# SAMV71_Xplained_Ultra_EDBG.net
KiCad netlist of a schematic drawn in Altium Designer
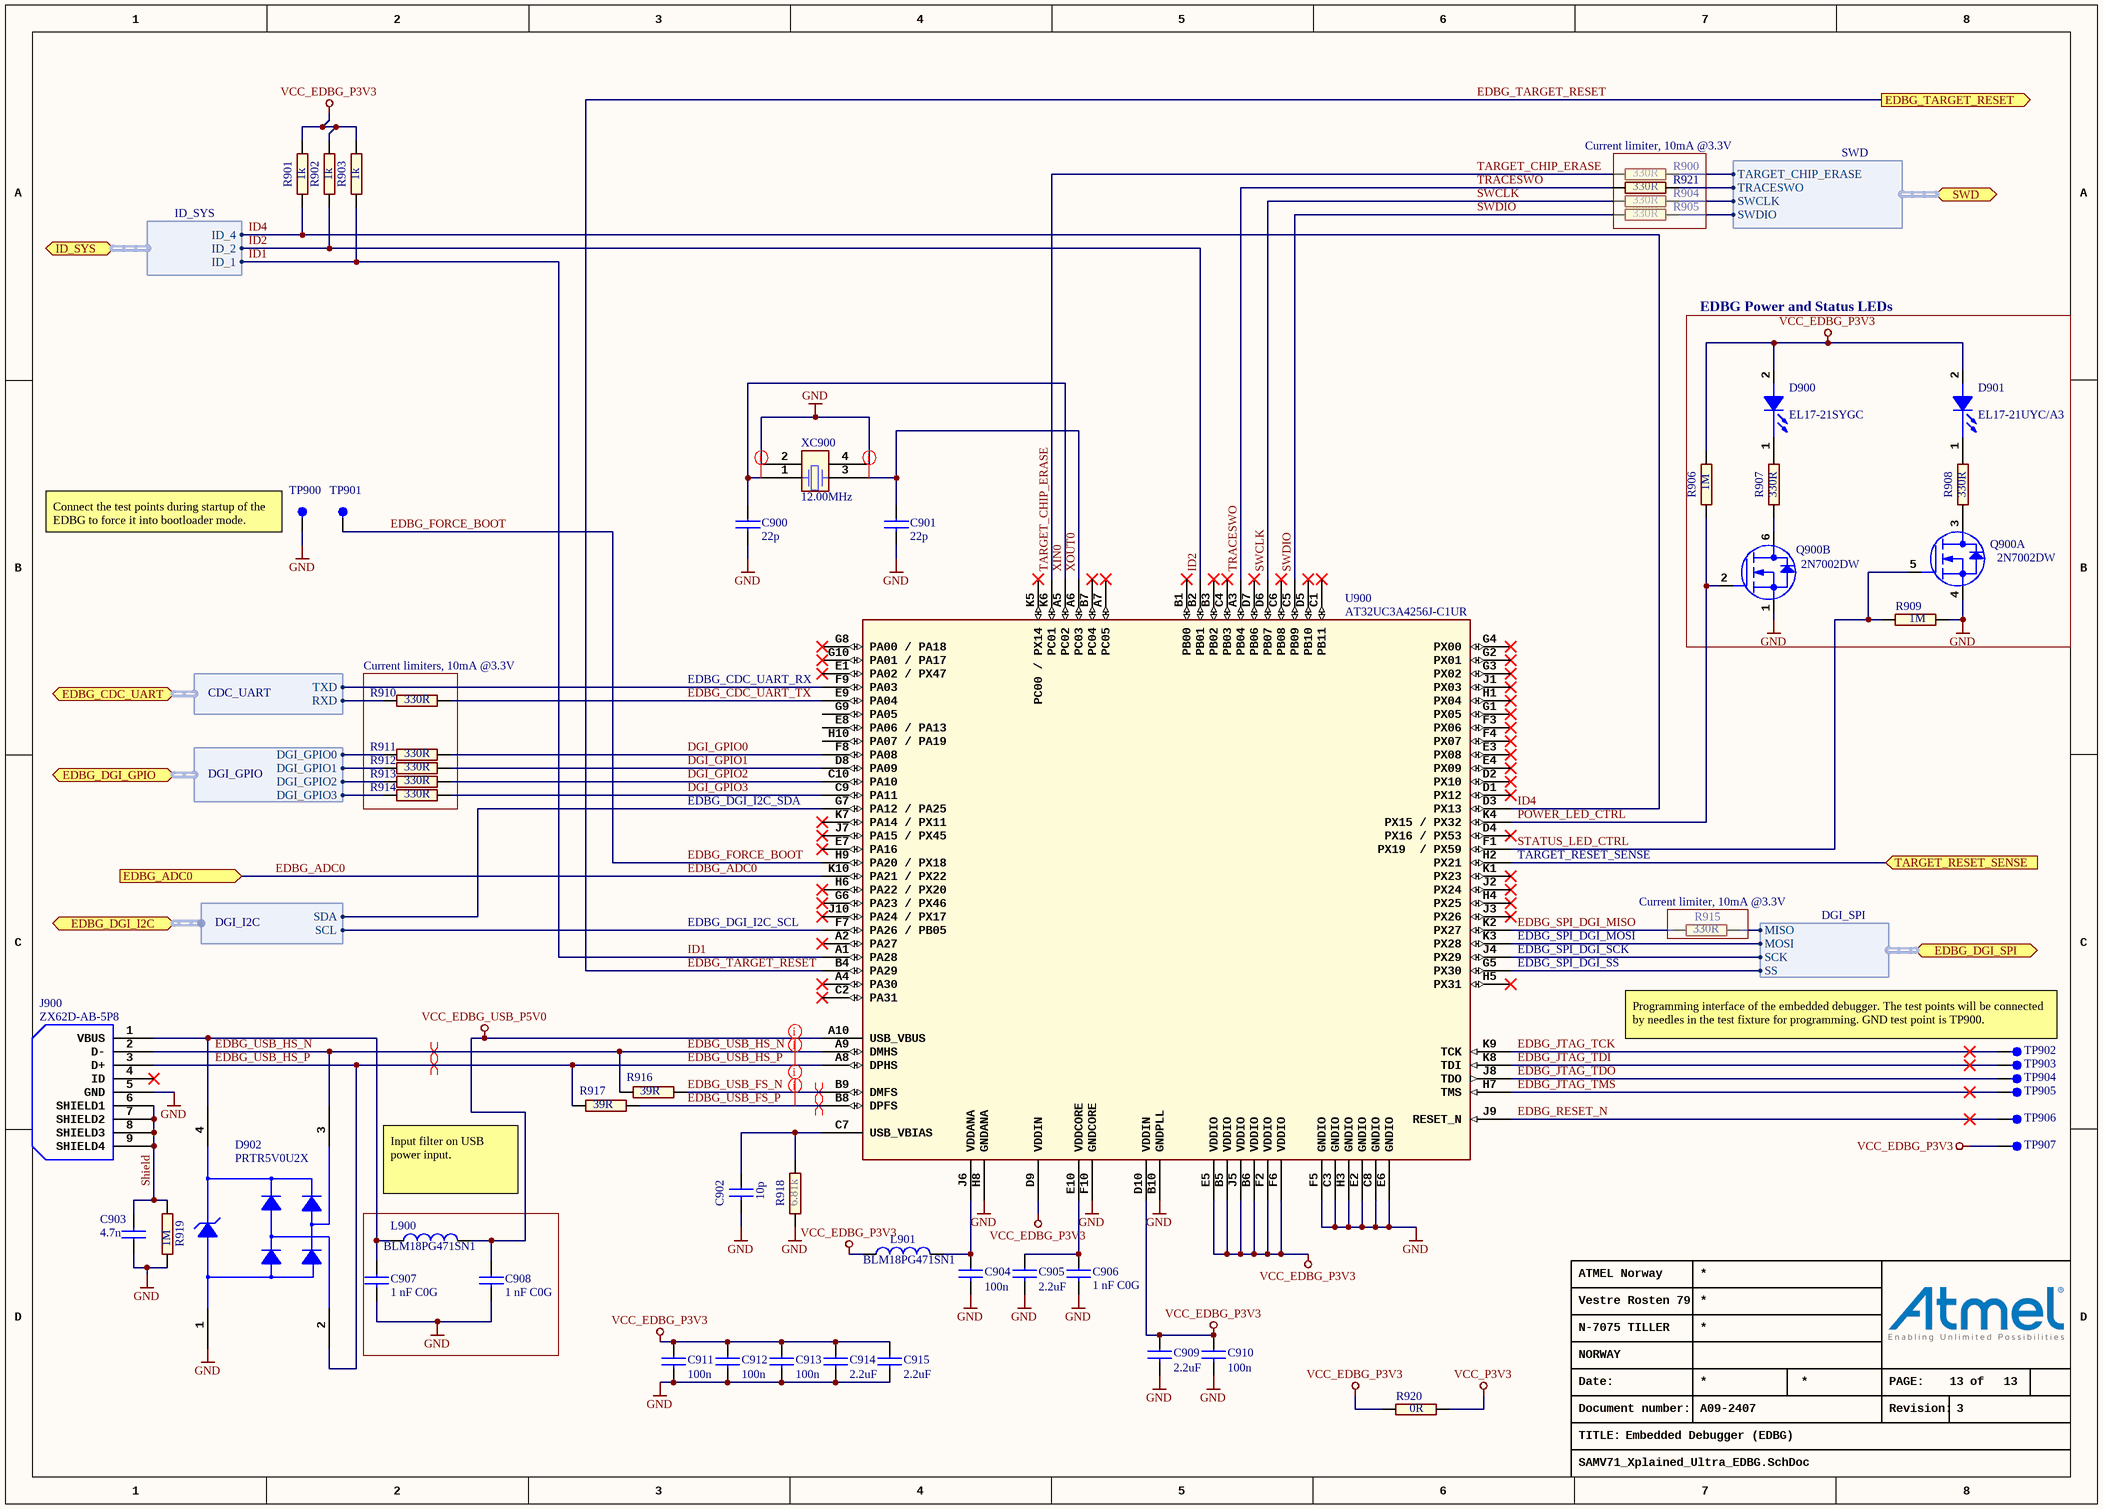
[diagram p0: SAMV71_Xplained_Ultra_EDBG.SchDoc]

(export (version "E")
  (design (tool "Eeschema 10.0.6"))
  (components
    (comp (ref "C900")
      (value "22p")
      (footprint "AP1-00053")
      (description "Ceramic capacitor, SMD 0402, NP0, 50V, +/-5%")
      (fields (field (name "TOLERANCE") "50V, +/-5%"))
      (libsource (lib "AltiumDbLib") (part "CAP-NONPOL"))
    )
    (comp (ref "C901")
      (value "22p")
      (footprint "AP1-00053")
      (description "Ceramic capacitor, SMD 0402, NP0, 50V, +/-5%")
      (fields (field (name "TOLERANCE") "50V, +/-5%"))
      (libsource (lib "AltiumDbLib") (part "CAP-NONPOL"))
    )
    (comp (ref "C902")
      (value "10p")
      (footprint "AP1-00053")
      (description "Ceramic capacitor, SMD 0402, NP0, 50V, +/-5%")
      (fields (field (name "TOLERANCE") "50V, +/-5%"))
      (libsource (lib "AltiumDbLib") (part "CAP-NONPOL"))
    )
    (comp (ref "C903")
      (value "4.7n")
      (footprint "AP1-00053")
      (description "Ceramic capacitor, SMD 0402, X7R, 25V, +/-10%")
      (fields (field (name "TOLERANCE") "25V, +/-10%"))
      (libsource (lib "AltiumDbLib") (part "CAP-NONPOL"))
    )
    (comp (ref "C904")
      (value "100n")
      (footprint "AP1-00053")
      (description "Ceramic capacitor, SMD 0402, X7R, 16V, +/-10%")
      (fields (field (name "TOLERANCE") "16V, +/-10%") (field (name "MANUFACTURER") "Kemet"))
      (libsource (lib "AltiumDbLib") (part "CAP-NONPOL"))
    )
    (comp (ref "C905")
      (value "2.2uF")
      (footprint "AP1-00053")
      (description "Ceramic capacitor, SMD 0402, X5R, 6.3V, +/-20%")
      (fields (field (name "TOLERANCE") "Â±20%") (field (name "MANUFACTURER") "Kemet"))
      (libsource (lib "AltiumDbLib") (part "CAP-NONPOL"))
    )
    (comp (ref "C906")
      (value "1 nF C0G")
      (footprint "AP1-00053")
      (description "Ceramic capacitor, SMD 0402, C0G, 50V, +/-5%")
      (fields (field (name "TOLERANCE") "5%") (field (name "MANUFACTURER") "Murata"))
      (libsource (lib "AltiumDbLib") (part "CAP-NONPOL"))
    )
    (comp (ref "C907")
      (value "1 nF C0G")
      (footprint "AP1-00053")
      (description "Ceramic capacitor, SMD 0402, C0G, 50V, +/-5%")
      (fields (field (name "TOLERANCE") "5%") (field (name "MANUFACTURER") "Murata"))
      (libsource (lib "AltiumDbLib") (part "CAP-NONPOL"))
    )
    (comp (ref "C908")
      (value "1 nF C0G")
      (footprint "AP1-00053")
      (description "Ceramic capacitor, SMD 0402, C0G, 50V, +/-5%")
      (fields (field (name "TOLERANCE") "5%") (field (name "MANUFACTURER") "Murata"))
      (libsource (lib "AltiumDbLib") (part "CAP-NONPOL"))
    )
    (comp (ref "C909")
      (value "2.2uF")
      (footprint "AP1-00053")
      (description "Ceramic capacitor, SMD 0402, X5R, 6.3V, +/-20%")
      (fields (field (name "TOLERANCE") "Â±20%") (field (name "MANUFACTURER") "Kemet"))
      (libsource (lib "AltiumDbLib") (part "CAP-NONPOL"))
    )
    (comp (ref "C910")
      (value "100n")
      (footprint "AP1-00053")
      (description "Ceramic capacitor, SMD 0402, X7R, 16V, +/-10%")
      (fields (field (name "TOLERANCE") "16V, +/-10%") (field (name "MANUFACTURER") "Kemet"))
      (libsource (lib "AltiumDbLib") (part "CAP-NONPOL"))
    )
    (comp (ref "C911")
      (value "100n")
      (footprint "AP1-00053")
      (description "Ceramic capacitor, SMD 0402, X7R, 16V, +/-10%")
      (fields (field (name "TOLERANCE") "16V, +/-10%") (field (name "MANUFACTURER") "Kemet"))
      (libsource (lib "AltiumDbLib") (part "CAP-NONPOL"))
    )
    (comp (ref "C912")
      (value "100n")
      (footprint "AP1-00053")
      (description "Ceramic capacitor, SMD 0402, X7R, 16V, +/-10%")
      (fields (field (name "TOLERANCE") "16V, +/-10%") (field (name "MANUFACTURER") "Kemet"))
      (libsource (lib "AltiumDbLib") (part "CAP-NONPOL"))
    )
    (comp (ref "C913")
      (value "100n")
      (footprint "AP1-00053")
      (description "Ceramic capacitor, SMD 0402, X7R, 16V, +/-10%")
      (fields (field (name "TOLERANCE") "16V, +/-10%") (field (name "MANUFACTURER") "Kemet"))
      (libsource (lib "AltiumDbLib") (part "CAP-NONPOL"))
    )
    (comp (ref "C914")
      (value "2.2uF")
      (footprint "AP1-00053")
      (description "Ceramic capacitor, SMD 0402, X5R, 6.3V, +/-20%")
      (fields (field (name "TOLERANCE") "Â±20%") (field (name "MANUFACTURER") "Kemet"))
      (libsource (lib "AltiumDbLib") (part "CAP-NONPOL"))
    )
    (comp (ref "C915")
      (value "2.2uF")
      (footprint "AP1-00053")
      (description "Ceramic capacitor, SMD 0402, X5R, 6.3V, +/-20%")
      (fields (field (name "TOLERANCE") "Â±20%") (field (name "MANUFACTURER") "Kemet"))
      (libsource (lib "AltiumDbLib") (part "CAP-NONPOL"))
    )
    (comp (ref "D900")
      (value "EL17-21SYGC")
      (footprint "AP4-00013")
      (description "LED, Green, Wave length=575nm, SMD 0805, ±70°")
      (fields (field (name "MANUFACTURER") "Everlight"))
      (libsource (lib "AltiumDbLib") (part "LED_12"))
    )
    (comp (ref "D901")
      (value "EL17-21UYC/A3")
      (footprint "AP4-00013")
      (description "LED, Yellow, Wave length=591nm, SMD 0805, ±70°")
      (fields (field (name "MANUFACTURER") "Everlight") (field (name "MPN") "17-21UYC/S530-A3/TR8"))
      (libsource (lib "AltiumDbLib") (part "LED_12"))
    )
    (comp (ref "D902")
      (value "PRTR5V0U2X")
      (footprint "AP4-00001")
      (description "Double rail-to-rail USB ESD protection diode")
      (fields (field (name "MANUFACTURER") "NXP"))
      (libsource (lib "AltiumDbLib") (part "PRTR5V0U2X"))
    )
    (comp (ref "J900")
      (value "ZX62D-AB-5P8")
      (footprint "AP8-00852")
      (description "Micro USB AB Connector, Standard SMT + DIP")
      (fields (field (name "MANUFACTURER") "HIROSE") (field (name "Comment") "2,000 pieces per reel"))
      (libsource (lib "AltiumDbLib") (part "USB_AB"))
    )
    (comp (ref "L900")
      (value "BLM18PG471SN1")
      (footprint "AP3-00005")
      (description "SMD RF inductor 0603. Z=470Ohm (@100MHz), Max R(dc)=0.65Ohm, Max current=1A")
      (fields (field (name "TOLERANCE") "±25%") (field (name "MANUFACTURER") "Murata"))
      (libsource (lib "AltiumDbLib") (part "INDUCTOR"))
    )
    (comp (ref "L901")
      (value "BLM18PG471SN1")
      (footprint "AP3-00005")
      (description "SMD RF inductor 0603. Z=470Ohm (@100MHz), Max R(dc)=0.65Ohm, Max current=1A")
      (fields (field (name "TOLERANCE") "±25%") (field (name "MANUFACTURER") "Murata"))
      (libsource (lib "AltiumDbLib") (part "INDUCTOR"))
    )
    (comp (ref "Q900")
      (value "2N7002DW")
      (footprint "AP5-00001")
      (description "Dual N-Channel MOSFET, 60V, 115mA cont,RDS(ON) < 7.5 Ohm @50mA@5V, SOT-363")
      (fields
        (field (name "MANUFACTURER") "Fairchild")
        (field (name "Comment") "Same as 2N7002 but with two MOSFETs in one package")
      )
      (libsource (lib "AltiumDbLib") (part "MOSFET_DUAL_N_S2G2D1S1G1D2"))
    )
    (comp (ref "R900")
      (value "330R")
      (footprint "AP2-00000")
      (description "Thick film resistor, SMD 0402, 1/16W, 1%")
      (fields (field (name "TOLERANCE") "1 %"))
      (libsource (lib "") (part "R2_2"))
    )
    (comp (ref "R901")
      (value "1k")
      (footprint "AP2-00000")
      (description "Thick film resistor, SMD 0402, 1/16W, 1%")
      (fields (field (name "TOLERANCE") "1 %"))
      (libsource (lib "") (part "R2_1"))
    )
    (comp (ref "R902")
      (value "1k")
      (footprint "AP2-00000")
      (description "Thick film resistor, SMD 0402, 1/16W, 1%")
      (fields (field (name "TOLERANCE") "1 %"))
      (libsource (lib "") (part "R2_1"))
    )
    (comp (ref "R903")
      (value "1k")
      (footprint "AP2-00000")
      (description "Thick film resistor, SMD 0402, 1/16W, 1%")
      (fields (field (name "TOLERANCE") "1 %"))
      (libsource (lib "") (part "R2_1"))
    )
    (comp (ref "R904")
      (value "330R")
      (footprint "AP2-00000")
      (description "Thick film resistor, SMD 0402, 1/16W, 1%")
      (fields (field (name "TOLERANCE") "1 %"))
      (libsource (lib "") (part "R2_2"))
    )
    (comp (ref "R905")
      (value "330R")
      (footprint "AP2-00000")
      (description "Thick film resistor, SMD 0402, 1/16W, 1%")
      (fields (field (name "TOLERANCE") "1 %"))
      (libsource (lib "") (part "R2_2"))
    )
    (comp (ref "R906")
      (value "1M")
      (footprint "AP2-00000")
      (description "Thick film resistor, SMD 0402, 1/16W, 1%")
      (fields (field (name "TOLERANCE") "1 %"))
      (libsource (lib "") (part "R2_1"))
    )
    (comp (ref "R907")
      (value "330R")
      (footprint "AP2-00000")
      (description "Thick film resistor, SMD 0402, 1/16W, 1%")
      (fields (field (name "TOLERANCE") "1 %"))
      (libsource (lib "") (part "R2_1"))
    )
    (comp (ref "R908")
      (value "330R")
      (footprint "AP2-00000")
      (description "Thick film resistor, SMD 0402, 1/16W, 1%")
      (fields (field (name "TOLERANCE") "1 %"))
      (libsource (lib "") (part "R2_1"))
    )
    (comp (ref "R909")
      (value "1M")
      (footprint "AP2-00000")
      (description "Thick film resistor, SMD 0402, 1/16W, 1%")
      (fields (field (name "TOLERANCE") "1 %"))
      (libsource (lib "") (part "R2_4"))
    )
    (comp (ref "R910")
      (value "330R")
      (footprint "AP2-00000")
      (description "Thick film resistor, SMD 0402, 1/16W, 1%")
      (fields (field (name "TOLERANCE") "1 %"))
      (libsource (lib "") (part "R2_2"))
    )
    (comp (ref "R911")
      (value "330R")
      (footprint "AP2-00000")
      (description "Thick film resistor, SMD 0402, 1/16W, 1%")
      (fields (field (name "TOLERANCE") "1 %"))
      (libsource (lib "") (part "R2_2"))
    )
    (comp (ref "R912")
      (value "330R")
      (footprint "AP2-00000")
      (description "Thick film resistor, SMD 0402, 1/16W, 1%")
      (fields (field (name "TOLERANCE") "1 %"))
      (libsource (lib "") (part "R2_2"))
    )
    (comp (ref "R913")
      (value "330R")
      (footprint "AP2-00000")
      (description "Thick film resistor, SMD 0402, 1/16W, 1%")
      (fields (field (name "TOLERANCE") "1 %"))
      (libsource (lib "") (part "R2_2"))
    )
    (comp (ref "R914")
      (value "330R")
      (footprint "AP2-00000")
      (description "Thick film resistor, SMD 0402, 1/16W, 1%")
      (fields (field (name "TOLERANCE") "1 %"))
      (libsource (lib "") (part "R2_2"))
    )
    (comp (ref "R915")
      (value "330R")
      (footprint "AP2-00000")
      (description "Thick film resistor, SMD 0402, 1/16W, 1%")
      (fields (field (name "TOLERANCE") "1 %"))
      (libsource (lib "") (part "R2_2"))
    )
    (comp (ref "R916")
      (value "39R")
      (footprint "AP2-00011")
      (description "Thick film resistor, SMD 0402, 1/16W, 1%")
      (fields (field (name "TOLERANCE") "1 %"))
      (libsource (lib "") (part "R2_3"))
    )
    (comp (ref "R917")
      (value "39R")
      (footprint "AP2-00011")
      (description "Thick film resistor, SMD 0402, 1/16W, 1%")
      (fields (field (name "TOLERANCE") "1 %"))
      (libsource (lib "") (part "R2_3"))
    )
    (comp (ref "R918")
      (value "6.81k")
      (footprint "AP2-00011")
      (description "Thick film resistor, SMD 0402, 1/16W, 1%")
      (fields (field (name "TOLERANCE") "1%"))
      (libsource (lib "") (part "R2_1"))
    )
    (comp (ref "R919")
      (value "1M")
      (footprint "AP2-00011")
      (description "Thick film resistor, SMD 0402, 1/16W, 1%")
      (fields (field (name "TOLERANCE") "1 %"))
      (libsource (lib "AltiumDbLib") (part "R2"))
    )
    (comp (ref "R920")
      (value "0R")
      (footprint "AP2-00000")
      (description "Thick film resistor, SMD 0402, 1/16W, 1%")
      (fields (field (name "TOLERANCE") "1 %") (field (name "MANUFACTURER") "(n/a)"))
      (libsource (lib "") (part "R2_2"))
    )
    (comp (ref "R921")
      (value "330R")
      (footprint "AP2-00000")
      (description "Thick film resistor, SMD 0402, 1/16W, 1%")
      (fields (field (name "TOLERANCE") "1 %"))
      (libsource (lib "") (part "R2_2"))
    )
    (comp (ref "TP900")
      (value "~")
      (footprint "AP8-00010")
      (description "Single SMD testpad")
      (libsource (lib "AltiumDbLib") (part "TESTPOINT"))
    )
    (comp (ref "TP901")
      (value "~")
      (footprint "AP8-00010")
      (description "Single SMD testpad")
      (libsource (lib "AltiumDbLib") (part "TESTPOINT"))
    )
    (comp (ref "TP902")
      (value "~")
      (footprint "AP8-00010")
      (description "Single SMD testpad")
      (libsource (lib "AltiumDbLib") (part "TESTPOINT"))
    )
    (comp (ref "TP903")
      (value "~")
      (footprint "AP8-00010")
      (description "Single SMD testpad")
      (libsource (lib "AltiumDbLib") (part "TESTPOINT"))
    )
    (comp (ref "TP904")
      (value "~")
      (footprint "AP8-00010")
      (description "Single SMD testpad")
      (libsource (lib "AltiumDbLib") (part "TESTPOINT"))
    )
    (comp (ref "TP905")
      (value "~")
      (footprint "AP8-00010")
      (description "Single SMD testpad")
      (libsource (lib "AltiumDbLib") (part "TESTPOINT"))
    )
    (comp (ref "TP906")
      (value "~")
      (footprint "AP8-00010")
      (description "Single SMD testpad")
      (libsource (lib "AltiumDbLib") (part "TESTPOINT"))
    )
    (comp (ref "TP907")
      (value "~")
      (footprint "AP8-00010")
      (description "Single SMD testpad")
      (libsource (lib "AltiumDbLib") (part "TESTPOINT"))
    )
    (comp (ref "U900")
      (value "AT32UC3A4256J-C1UR")
      (footprint "AP6-00206")
      (description "AVR 32-bit RISC MCU")
      (fields (field (name "MANUFACTURER") "ATMEL") (field (name "Comment") "100 ball VFBGA"))
      (libsource (lib "AltiumDbLib") (part "AT32UC3A4_VFBGA"))
    )
    (comp (ref "XC900")
      (value "12.00MHz")
      (footprint "AP7-00039")
      (description "Fox FQ5032B 12.0MHz SMD crystal 738B-12")
      (fields (field (name "TOLERANCE") "Â±30ppm") (field (name "MANUFACTURER") "Fox  Electronics"))
      (libsource (lib "AltiumDbLib") (part "CRYSTAL1324"))
    )
  )
  (nets
    (net (code "7") (name "/DGI_GPIO0") (class "Default")
      (node (ref "R911") (pin "2") (pinfunction "2_2") (pintype "passive"))
      (node (ref "U900") (pin "F8") (pinfunction "PA08_F8") (pintype "bidirectional"))
    )
    (net (code "8") (name "/DGI_GPIO1") (class "Default")
      (node (ref "R912") (pin "2") (pinfunction "2_2") (pintype "passive"))
      (node (ref "U900") (pin "D8") (pinfunction "PA09_D8") (pintype "bidirectional"))
    )
    (net (code "9") (name "/DGI_GPIO2") (class "Default")
      (node (ref "R913") (pin "2") (pinfunction "2_2") (pintype "passive"))
      (node (ref "U900") (pin "C10") (pinfunction "PA10_C10") (pintype "bidirectional"))
    )
    (net (code "10") (name "/DGI_GPIO3") (class "Default")
      (node (ref "R914") (pin "2") (pinfunction "2_2") (pintype "passive"))
      (node (ref "U900") (pin "C9") (pinfunction "PA11_C9") (pintype "bidirectional"))
    )
    (net (code "11") (name "/EDBG_ADC0") (class "Default")
      (node (ref "U900") (pin "K10") (pinfunction "PA21_/_PX22_K10") (pintype "bidirectional"))
    )
    (net (code "12") (name "/EDBG_CDC_UART_TX") (class "Default")
      (node (ref "R910") (pin "2") (pinfunction "2_2") (pintype "passive"))
      (node (ref "U900") (pin "E9") (pinfunction "PA04_E9") (pintype "bidirectional"))
    )
    (net (code "13") (name "/EDBG_FORCE_BOOT") (class "Default")
      (node (ref "TP901") (pin "1") (pinfunction "1_1") (pintype "passive"))
      (node (ref "U900") (pin "H9") (pinfunction "PA20_/_PX18_H9") (pintype "bidirectional"))
    )
    (net (code "14") (name "/EDBG_JTAG_TCK") (class "Default")
      (node (ref "TP902") (pin "1") (pinfunction "1_1") (pintype "passive"))
      (node (ref "U900") (pin "K9") (pinfunction "TCK_K9") (pintype "input"))
    )
    (net (code "15") (name "/EDBG_JTAG_TDI") (class "Default")
      (node (ref "TP903") (pin "1") (pinfunction "1_1") (pintype "passive"))
      (node (ref "U900") (pin "K8") (pinfunction "TDI_K8") (pintype "input"))
    )
    (net (code "16") (name "/EDBG_JTAG_TDO") (class "Default")
      (node (ref "TP904") (pin "1") (pinfunction "1_1") (pintype "passive"))
      (node (ref "U900") (pin "J8") (pinfunction "TDO_J8") (pintype "output"))
    )
    (net (code "17") (name "/EDBG_JTAG_TMS") (class "Default")
      (node (ref "TP905") (pin "1") (pinfunction "1_1") (pintype "passive"))
      (node (ref "U900") (pin "H7") (pinfunction "TMS_H7") (pintype "input"))
    )
    (net (code "18") (name "/EDBG_RESET_N") (class "Default")
      (node (ref "TP906") (pin "1") (pinfunction "1_1") (pintype "passive"))
      (node (ref "U900") (pin "J9") (pinfunction "RESET_N_J9") (pintype "input"))
    )
    (net (code "19") (name "/EDBG_SPI_DGI_MISO") (class "Default")
      (node (ref "R915") (pin "1") (pinfunction "1_1") (pintype "passive"))
      (node (ref "U900") (pin "K2") (pinfunction "PX27_K2") (pintype "bidirectional"))
    )
    (net (code "20") (name "/EDBG_TARGET_RESET") (class "Default")
      (node (ref "U900") (pin "B4") (pinfunction "PA29_B4") (pintype "bidirectional"))
    )
    (net (code "21") (name "/EDBG_USB_FS_N") (class "Default")
      (node (ref "R916") (pin "2") (pinfunction "2_2") (pintype "passive"))
      (node (ref "U900") (pin "B9") (pinfunction "DMFS_B9") (pintype "bidirectional"))
    )
    (net (code "22") (name "/EDBG_USB_FS_P") (class "Default")
      (node (ref "R917") (pin "2") (pinfunction "2_2") (pintype "passive"))
      (node (ref "U900") (pin "B8") (pinfunction "DPFS_B8") (pintype "bidirectional"))
    )
    (net (code "23") (name "/EDBG_USB_HS_N") (class "Default")
      (node (ref "D902") (pin "3") (pinfunction "I/O_2_3") (pintype "passive"))
      (node (ref "J900") (pin "2") (pinfunction "D-_2") (pintype "passive"))
      (node (ref "R916") (pin "1") (pinfunction "1_1") (pintype "passive"))
      (node (ref "U900") (pin "A9") (pinfunction "DMHS_A9") (pintype "bidirectional"))
    )
    (net (code "24") (name "/EDBG_USB_HS_P") (class "Default")
      (node (ref "D902") (pin "2") (pinfunction "I/O_1_2") (pintype "passive"))
      (node (ref "J900") (pin "3") (pinfunction "D+_3") (pintype "passive"))
      (node (ref "R917") (pin "1") (pinfunction "1_1") (pintype "passive"))
      (node (ref "U900") (pin "A8") (pinfunction "DPHS_A8") (pintype "bidirectional"))
    )
    (net (code "25") (name "/ID1") (class "Default")
      (node (ref "R903") (pin "1") (pinfunction "1_1") (pintype "passive"))
      (node (ref "U900") (pin "A1") (pinfunction "PA28_A1") (pintype "bidirectional"))
    )
    (net (code "26") (name "/ID2") (class "Default")
      (node (ref "R902") (pin "1") (pinfunction "1_1") (pintype "passive"))
      (node (ref "U900") (pin "B2") (pinfunction "PB01_B2") (pintype "bidirectional"))
    )
    (net (code "27") (name "/ID4") (class "Default")
      (node (ref "R901") (pin "1") (pinfunction "1_1") (pintype "passive"))
      (node (ref "U900") (pin "D3") (pinfunction "PX13_D3") (pintype "bidirectional"))
    )
    (net (code "28") (name "/MISO") (class "Default")
      (node (ref "R915") (pin "2") (pinfunction "2_2") (pintype "passive"))
    )
    (net (code "29") (name "/MOSI") (class "Default")
      (node (ref "U900") (pin "K3") (pinfunction "PX28_K3") (pintype "bidirectional"))
    )
    (net (code "30") (name "/POWER_LED_CTRL") (class "Default")
      (node (ref "Q900") (pin "2") (pinfunction "G2_2") (pintype "passive"))
      (node (ref "R906") (pin "1") (pinfunction "1_1") (pintype "passive"))
      (node (ref "U900") (pin "K4") (pinfunction "PX15_/_PX32_K4") (pintype "bidirectional"))
    )
    (net (code "31") (name "/RXD") (class "Default")
      (node (ref "R910") (pin "1") (pinfunction "1_1") (pintype "passive"))
    )
    (net (code "32") (name "/SCK") (class "Default")
      (node (ref "U900") (pin "J4") (pinfunction "PX29_J4") (pintype "bidirectional"))
    )
    (net (code "33") (name "/SCL") (class "Default")
      (node (ref "U900") (pin "F7") (pinfunction "PA26_/_PB05_F7") (pintype "bidirectional"))
    )
    (net (code "34") (name "/SDA") (class "Default")
      (node (ref "U900") (pin "G7") (pinfunction "PA12_/_PA25_G7") (pintype "bidirectional"))
    )
    (net (code "35") (name "/SS") (class "Default")
      (node (ref "U900") (pin "G5") (pinfunction "PX30_G5") (pintype "bidirectional"))
    )
    (net (code "36") (name "/STATUS_LED_CTRL") (class "Default")
      (node (ref "Q900") (pin "5") (pinfunction "G1_5") (pintype "passive"))
      (node (ref "R909") (pin "2") (pinfunction "2_2") (pintype "passive"))
      (node (ref "U900") (pin "F1") (pinfunction "PX19__/_PX59_F1") (pintype "bidirectional"))
    )
    (net (code "37") (name "/SWCLK") (class "Default")
      (node (ref "R904") (pin "1") (pinfunction "1_1") (pintype "passive"))
      (node (ref "U900") (pin "D6") (pinfunction "PB07_D6") (pintype "bidirectional"))
    )
    (net (code "38") (name "/SWDIO") (class "Default")
      (node (ref "R905") (pin "1") (pinfunction "1_1") (pintype "passive"))
      (node (ref "U900") (pin "C5") (pinfunction "PB09_C5") (pintype "bidirectional"))
    )
    (net (code "39") (name "/Shield") (class "Default")
      (node (ref "C903") (pin "2") (pinfunction "2_2") (pintype "passive"))
      (node (ref "J900") (pin "6") (pinfunction "SHIELD1_6") (pintype "passive"))
      (node (ref "J900") (pin "7") (pinfunction "SHIELD2_7") (pintype "passive"))
      (node (ref "J900") (pin "8") (pinfunction "SHIELD3_8") (pintype "passive"))
      (node (ref "J900") (pin "9") (pinfunction "SHIELD4_9") (pintype "passive"))
      (node (ref "R919") (pin "2") (pinfunction "2_2") (pintype "passive"))
    )
    (net (code "40") (name "/TARGET_CHIP_ERASE") (class "Default")
      (node (ref "R900") (pin "1") (pinfunction "1_1") (pintype "passive"))
      (node (ref "U900") (pin "K6") (pinfunction "PC01_K6") (pintype "bidirectional"))
    )
    (net (code "41") (name "/TARGET_RESET_SENSE") (class "Default")
      (node (ref "U900") (pin "H2") (pinfunction "PX21_H2") (pintype "bidirectional"))
    )
    (net (code "42") (name "/TRACESWO") (class "Default")
      (node (ref "R921") (pin "1") (pinfunction "1_1") (pintype "passive"))
      (node (ref "U900") (pin "A3") (pinfunction "PB04_A3") (pintype "bidirectional"))
    )
    (net (code "43") (name "/TXD") (class "Default")
      (node (ref "U900") (pin "F9") (pinfunction "PA03_F9") (pintype "bidirectional"))
    )
    (net (code "44") (name "/XIN0") (class "Default")
      (node (ref "C900") (pin "1") (pinfunction "1_1") (pintype "passive"))
      (node (ref "U900") (pin "A5") (pinfunction "PC02_A5") (pintype "bidirectional"))
      (node (ref "XC900") (pin "1") (pinfunction "1_1") (pintype "passive"))
    )
    (net (code "45") (name "/XOUT0") (class "Default")
      (node (ref "C901") (pin "1") (pinfunction "1_1") (pintype "passive"))
      (node (ref "U900") (pin "A6") (pinfunction "PC03_A6") (pintype "bidirectional"))
      (node (ref "XC900") (pin "3") (pinfunction "3_3") (pintype "passive"))
    )
    (net (code "52") (name "GND") (class "Default")
      (node (ref "C900") (pin "2") (pinfunction "2_2") (pintype "passive"))
      (node (ref "C901") (pin "2") (pinfunction "2_2") (pintype "passive"))
      (node (ref "C902") (pin "2") (pinfunction "2_2") (pintype "passive"))
      (node (ref "C903") (pin "1") (pinfunction "1_1") (pintype "passive"))
      (node (ref "C904") (pin "2") (pinfunction "2_2") (pintype "passive"))
      (node (ref "C905") (pin "2") (pinfunction "2_2") (pintype "passive"))
      (node (ref "C906") (pin "2") (pinfunction "2_2") (pintype "passive"))
      (node (ref "C907") (pin "2") (pinfunction "2_2") (pintype "passive"))
      (node (ref "C908") (pin "2") (pinfunction "2_2") (pintype "passive"))
      (node (ref "C909") (pin "2") (pinfunction "2_2") (pintype "passive"))
      (node (ref "C910") (pin "2") (pinfunction "2_2") (pintype "passive"))
      (node (ref "C911") (pin "2") (pinfunction "2_2") (pintype "passive"))
      (node (ref "C912") (pin "2") (pinfunction "2_2") (pintype "passive"))
      (node (ref "C913") (pin "2") (pinfunction "2_2") (pintype "passive"))
      (node (ref "C914") (pin "2") (pinfunction "2_2") (pintype "passive"))
      (node (ref "C915") (pin "2") (pinfunction "2_2") (pintype "passive"))
      (node (ref "D902") (pin "1") (pinfunction "GND_1") (pintype "passive"))
      (node (ref "J900") (pin "5") (pinfunction "GND_5") (pintype "passive"))
      (node (ref "Q900") (pin "1") (pinfunction "S2_1") (pintype "passive"))
      (node (ref "Q900") (pin "4") (pinfunction "S1_4") (pintype "passive"))
      (node (ref "R909") (pin "1") (pinfunction "1_1") (pintype "passive"))
      (node (ref "R918") (pin "1") (pinfunction "1_1") (pintype "passive"))
      (node (ref "R919") (pin "1") (pinfunction "1_1") (pintype "passive"))
      (node (ref "TP900") (pin "1") (pinfunction "1_1") (pintype "passive"))
      (node (ref "U900") (pin "B10") (pinfunction "GNDPLL_B10") (pintype "power_in"))
      (node (ref "U900") (pin "C3") (pinfunction "GNDIO_C3") (pintype "power_in"))
      (node (ref "U900") (pin "C8") (pinfunction "GNDIO_C8") (pintype "power_in"))
      (node (ref "U900") (pin "E2") (pinfunction "GNDIO_E2") (pintype "power_in"))
      (node (ref "U900") (pin "E6") (pinfunction "GNDIO_E6") (pintype "power_in"))
      (node (ref "U900") (pin "F10") (pinfunction "GNDCORE_F10") (pintype "power_in"))
      (node (ref "U900") (pin "F5") (pinfunction "GNDIO_F5") (pintype "power_in"))
      (node (ref "U900") (pin "H3") (pinfunction "GNDIO_H3") (pintype "power_in"))
      (node (ref "U900") (pin "H8") (pinfunction "GNDANA_H8") (pintype "power_in"))
      (node (ref "XC900") (pin "2") (pinfunction "2_2") (pintype "passive"))
      (node (ref "XC900") (pin "4") (pinfunction "4_4") (pintype "passive"))
    )
    (net (code "53") (name "Net-(D900-CATHODE)") (class "Default")
      (node (ref "D900") (pin "1") (pinfunction "CATHODE_1") (pintype "passive"))
      (node (ref "R907") (pin "2") (pinfunction "2_2") (pintype "passive"))
    )
    (net (code "54") (name "Net-(D901-CATHODE)") (class "Default")
      (node (ref "D901") (pin "1") (pinfunction "CATHODE_1") (pintype "passive"))
      (node (ref "R908") (pin "2") (pinfunction "2_2") (pintype "passive"))
    )
    (net (code "55") (name "Net-(D902-VCC)") (class "Default")
      (node (ref "C907") (pin "1") (pinfunction "1_1") (pintype "passive"))
      (node (ref "D902") (pin "4") (pinfunction "VCC_4") (pintype "passive"))
      (node (ref "J900") (pin "1") (pinfunction "VBUS_1") (pintype "passive"))
      (node (ref "L900") (pin "1") (pinfunction "1_1") (pintype "passive"))
    )
    (net (code "56") (name "Net-(Q900A-D1)") (class "Default")
      (node (ref "Q900") (pin "3") (pinfunction "D1_3") (pintype "passive"))
      (node (ref "R908") (pin "1") (pinfunction "1_1") (pintype "passive"))
    )
    (net (code "57") (name "Net-(Q900B-D2)") (class "Default")
      (node (ref "Q900") (pin "6") (pinfunction "D2_6") (pintype "passive"))
      (node (ref "R907") (pin "1") (pinfunction "1_1") (pintype "passive"))
    )
    (net (code "58") (name "Net-(U900-USB_VBIAS)") (class "Default")
      (node (ref "C902") (pin "1") (pinfunction "1_1") (pintype "passive"))
      (node (ref "R918") (pin "2") (pinfunction "2_2") (pintype "passive"))
      (node (ref "U900") (pin "C7") (pinfunction "USB_VBIAS_C7") (pintype "power_in"))
    )
    (net (code "59") (name "Net-(U900-VDDANA)") (class "Default")
      (node (ref "C904") (pin "1") (pinfunction "1_1") (pintype "passive"))
      (node (ref "L901") (pin "2") (pinfunction "2_2") (pintype "passive"))
      (node (ref "U900") (pin "J6") (pinfunction "VDDANA_J6") (pintype "power_in"))
    )
    (net (code "60") (name "Net-(U900-VDDCORE)") (class "Default")
      (node (ref "C905") (pin "1") (pinfunction "1_1") (pintype "passive"))
      (node (ref "C906") (pin "1") (pinfunction "1_1") (pintype "passive"))
      (node (ref "U900") (pin "E10") (pinfunction "VDDCORE_E10") (pintype "power_in"))
    )
    (net (code "61") (name "VCC_EDBG_P3V3") (class "Default")
      (node (ref "C909") (pin "1") (pinfunction "1_1") (pintype "passive"))
      (node (ref "C910") (pin "1") (pinfunction "1_1") (pintype "passive"))
      (node (ref "C911") (pin "1") (pinfunction "1_1") (pintype "passive"))
      (node (ref "C912") (pin "1") (pinfunction "1_1") (pintype "passive"))
      (node (ref "C913") (pin "1") (pinfunction "1_1") (pintype "passive"))
      (node (ref "C914") (pin "1") (pinfunction "1_1") (pintype "passive"))
      (node (ref "C915") (pin "1") (pinfunction "1_1") (pintype "passive"))
      (node (ref "D900") (pin "2") (pinfunction "ANODE_2") (pintype "passive"))
      (node (ref "D901") (pin "2") (pinfunction "ANODE_2") (pintype "passive"))
      (node (ref "L901") (pin "1") (pinfunction "1_1") (pintype "passive"))
      (node (ref "R901") (pin "2") (pinfunction "2_2") (pintype "passive"))
      (node (ref "R902") (pin "2") (pinfunction "2_2") (pintype "passive"))
      (node (ref "R903") (pin "2") (pinfunction "2_2") (pintype "passive"))
      (node (ref "R906") (pin "2") (pinfunction "2_2") (pintype "passive"))
      (node (ref "R920") (pin "1") (pinfunction "1_1") (pintype "passive"))
      (node (ref "TP907") (pin "1") (pinfunction "1_1") (pintype "passive"))
      (node (ref "U900") (pin "B5") (pinfunction "VDDIO_B5") (pintype "power_in"))
      (node (ref "U900") (pin "B6") (pinfunction "VDDIO_B6") (pintype "power_in"))
      (node (ref "U900") (pin "D10") (pinfunction "VDDIN_D10") (pintype "power_in"))
      (node (ref "U900") (pin "D9") (pinfunction "VDDIN_D9") (pintype "power_in"))
      (node (ref "U900") (pin "E5") (pinfunction "VDDIO_E5") (pintype "power_in"))
      (node (ref "U900") (pin "F2") (pinfunction "VDDIO_F2") (pintype "power_in"))
      (node (ref "U900") (pin "F6") (pinfunction "VDDIO_F6") (pintype "power_in"))
      (node (ref "U900") (pin "J5") (pinfunction "VDDIO_J5") (pintype "power_in"))
    )
    (net (code "62") (name "VCC_EDBG_USB_P5V0") (class "Default")
      (node (ref "C908") (pin "1") (pinfunction "1_1") (pintype "passive"))
      (node (ref "L900") (pin "2") (pinfunction "2_2") (pintype "passive"))
      (node (ref "U900") (pin "A10") (pinfunction "USB_VBUS_A10") (pintype "power_in"))
    )
    (net (code "63") (name "VCC_P3V3") (class "Default")
      (node (ref "R920") (pin "2") (pinfunction "2_2") (pintype "passive"))
    )
    (net (code "64") (name "unconnected-(J900-ID-Pad4)") (class "Default")
      (node (ref "J900") (pin "4") (pinfunction "ID_4") (pintype "passive+no_connect"))
    )
    (net (code "65") (name "unconnected-(R900-Pad2)") (class "Default")
      (node (ref "R900") (pin "2") (pinfunction "2_2") (pintype "passive"))
    )
    (net (code "66") (name "unconnected-(R904-Pad2)") (class "Default")
      (node (ref "R904") (pin "2") (pinfunction "2_2") (pintype "passive"))
    )
    (net (code "67") (name "unconnected-(R905-Pad2)") (class "Default")
      (node (ref "R905") (pin "2") (pinfunction "2_2") (pintype "passive"))
    )
    (net (code "68") (name "unconnected-(R911-Pad1)") (class "Default")
      (node (ref "R911") (pin "1") (pinfunction "1_1") (pintype "passive"))
    )
    (net (code "69") (name "unconnected-(R912-Pad1)") (class "Default")
      (node (ref "R912") (pin "1") (pinfunction "1_1") (pintype "passive"))
    )
    (net (code "70") (name "unconnected-(R913-Pad1)") (class "Default")
      (node (ref "R913") (pin "1") (pinfunction "1_1") (pintype "passive"))
    )
    (net (code "71") (name "unconnected-(R914-Pad1)") (class "Default")
      (node (ref "R914") (pin "1") (pinfunction "1_1") (pintype "passive"))
    )
    (net (code "72") (name "unconnected-(R921-Pad2)") (class "Default")
      (node (ref "R921") (pin "2") (pinfunction "2_2") (pintype "passive"))
    )
    (net (code "73") (name "unconnected-(U900-PA00_{slash}_PA18-PadG8)") (class "Default")
      (node (ref "U900") (pin "G8") (pinfunction "PA00_/_PA18_G8") (pintype "bidirectional+no_connect"))
    )
    (net (code "74") (name "unconnected-(U900-PA01_{slash}_PA17-PadG10)") (class "Default")
      (node (ref "U900") (pin "G10") (pinfunction "PA01_/_PA17_G10") (pintype "bidirectional+no_connect"))
    )
    (net (code "75") (name "unconnected-(U900-PA02_{slash}_PX47-PadE1)") (class "Default")
      (node (ref "U900") (pin "E1") (pinfunction "PA02_/_PX47_E1") (pintype "bidirectional+no_connect"))
    )
    (net (code "76") (name "unconnected-(U900-PA05-PadG9)") (class "Default")
      (node (ref "U900") (pin "G9") (pinfunction "PA05_G9") (pintype "bidirectional"))
    )
    (net (code "77") (name "unconnected-(U900-PA06_{slash}_PA13-PadE8)") (class "Default")
      (node (ref "U900") (pin "E8") (pinfunction "PA06_/_PA13_E8") (pintype "bidirectional"))
    )
    (net (code "78") (name "unconnected-(U900-PA07_{slash}_PA19-PadH10)") (class "Default")
      (node (ref "U900") (pin "H10") (pinfunction "PA07_/_PA19_H10") (pintype "bidirectional"))
    )
    (net (code "79") (name "unconnected-(U900-PA14_{slash}_PX11-PadK7)") (class "Default")
      (node (ref "U900") (pin "K7") (pinfunction "PA14_/_PX11_K7") (pintype "bidirectional+no_connect"))
    )
    (net (code "80") (name "unconnected-(U900-PA15_{slash}_PX45-PadJ7)") (class "Default")
      (node (ref "U900") (pin "J7") (pinfunction "PA15_/_PX45_J7") (pintype "bidirectional+no_connect"))
    )
    (net (code "81") (name "unconnected-(U900-PA16-PadE7)") (class "Default")
      (node (ref "U900") (pin "E7") (pinfunction "PA16_E7") (pintype "bidirectional+no_connect"))
    )
    (net (code "82") (name "unconnected-(U900-PA22_{slash}_PX20-PadH6)") (class "Default")
      (node (ref "U900") (pin "H6") (pinfunction "PA22_/_PX20_H6") (pintype "bidirectional+no_connect"))
    )
    (net (code "83") (name "unconnected-(U900-PA23_{slash}_PX46-PadG6)") (class "Default")
      (node (ref "U900") (pin "G6") (pinfunction "PA23_/_PX46_G6") (pintype "bidirectional+no_connect"))
    )
    (net (code "84") (name "unconnected-(U900-PA24_{slash}_PX17-PadJ10)") (class "Default")
      (node (ref "U900") (pin "J10") (pinfunction "PA24_/_PX17_J10") (pintype "bidirectional+no_connect"))
    )
    (net (code "85") (name "unconnected-(U900-PA27-PadA2)") (class "Default")
      (node (ref "U900") (pin "A2") (pinfunction "PA27_A2") (pintype "bidirectional+no_connect"))
    )
    (net (code "86") (name "unconnected-(U900-PA30-PadA4)") (class "Default")
      (node (ref "U900") (pin "A4") (pinfunction "PA30_A4") (pintype "bidirectional+no_connect"))
    )
    (net (code "87") (name "unconnected-(U900-PA31-PadC2)") (class "Default")
      (node (ref "U900") (pin "C2") (pinfunction "PA31_C2") (pintype "bidirectional+no_connect"))
    )
    (net (code "88") (name "unconnected-(U900-PB00-PadB1)") (class "Default")
      (node (ref "U900") (pin "B1") (pinfunction "PB00_B1") (pintype "bidirectional+no_connect"))
    )
    (net (code "89") (name "unconnected-(U900-PB02-PadB3)") (class "Default")
      (node (ref "U900") (pin "B3") (pinfunction "PB02_B3") (pintype "bidirectional+no_connect"))
    )
    (net (code "90") (name "unconnected-(U900-PB03-PadC4)") (class "Default")
      (node (ref "U900") (pin "C4") (pinfunction "PB03_C4") (pintype "bidirectional+no_connect"))
    )
    (net (code "91") (name "unconnected-(U900-PB06-PadD7)") (class "Default")
      (node (ref "U900") (pin "D7") (pinfunction "PB06_D7") (pintype "bidirectional+no_connect"))
    )
    (net (code "92") (name "unconnected-(U900-PB08-PadC6)") (class "Default")
      (node (ref "U900") (pin "C6") (pinfunction "PB08_C6") (pintype "bidirectional+no_connect"))
    )
    (net (code "93") (name "unconnected-(U900-PB10-PadD5)") (class "Default")
      (node (ref "U900") (pin "D5") (pinfunction "PB10_D5") (pintype "bidirectional+no_connect"))
    )
    (net (code "94") (name "unconnected-(U900-PB11-PadC1)") (class "Default")
      (node (ref "U900") (pin "C1") (pinfunction "PB11_C1") (pintype "bidirectional+no_connect"))
    )
    (net (code "95") (name "unconnected-(U900-PC00_{slash}_PX14-PadK5)") (class "Default")
      (node (ref "U900") (pin "K5") (pinfunction "PC00_/_PX14_K5") (pintype "bidirectional+no_connect"))
    )
    (net (code "96") (name "unconnected-(U900-PC04-PadB7)") (class "Default")
      (node (ref "U900") (pin "B7") (pinfunction "PC04_B7") (pintype "bidirectional+no_connect"))
    )
    (net (code "97") (name "unconnected-(U900-PC05-PadA7)") (class "Default")
      (node (ref "U900") (pin "A7") (pinfunction "PC05_A7") (pintype "bidirectional+no_connect"))
    )
    (net (code "98") (name "unconnected-(U900-PX00-PadG4)") (class "Default")
      (node (ref "U900") (pin "G4") (pinfunction "PX00_G4") (pintype "bidirectional+no_connect"))
    )
    (net (code "99") (name "unconnected-(U900-PX01-PadG2)") (class "Default")
      (node (ref "U900") (pin "G2") (pinfunction "PX01_G2") (pintype "bidirectional+no_connect"))
    )
    (net (code "100") (name "unconnected-(U900-PX02-PadG3)") (class "Default")
      (node (ref "U900") (pin "G3") (pinfunction "PX02_G3") (pintype "bidirectional+no_connect"))
    )
    (net (code "101") (name "unconnected-(U900-PX03-PadJ1)") (class "Default")
      (node (ref "U900") (pin "J1") (pinfunction "PX03_J1") (pintype "bidirectional+no_connect"))
    )
    (net (code "102") (name "unconnected-(U900-PX04-PadH1)") (class "Default")
      (node (ref "U900") (pin "H1") (pinfunction "PX04_H1") (pintype "bidirectional+no_connect"))
    )
    (net (code "103") (name "unconnected-(U900-PX05-PadG1)") (class "Default")
      (node (ref "U900") (pin "G1") (pinfunction "PX05_G1") (pintype "bidirectional+no_connect"))
    )
    (net (code "104") (name "unconnected-(U900-PX06-PadF3)") (class "Default")
      (node (ref "U900") (pin "F3") (pinfunction "PX06_F3") (pintype "bidirectional+no_connect"))
    )
    (net (code "105") (name "unconnected-(U900-PX07-PadF4)") (class "Default")
      (node (ref "U900") (pin "F4") (pinfunction "PX07_F4") (pintype "bidirectional+no_connect"))
    )
    (net (code "106") (name "unconnected-(U900-PX08-PadE3)") (class "Default")
      (node (ref "U900") (pin "E3") (pinfunction "PX08_E3") (pintype "bidirectional+no_connect"))
    )
    (net (code "107") (name "unconnected-(U900-PX09-PadE4)") (class "Default")
      (node (ref "U900") (pin "E4") (pinfunction "PX09_E4") (pintype "bidirectional+no_connect"))
    )
    (net (code "108") (name "unconnected-(U900-PX10-PadD2)") (class "Default")
      (node (ref "U900") (pin "D2") (pinfunction "PX10_D2") (pintype "bidirectional+no_connect"))
    )
    (net (code "109") (name "unconnected-(U900-PX12-PadD1)") (class "Default")
      (node (ref "U900") (pin "D1") (pinfunction "PX12_D1") (pintype "bidirectional+no_connect"))
    )
    (net (code "110") (name "unconnected-(U900-PX16_{slash}_PX53-PadD4)") (class "Default")
      (node (ref "U900") (pin "D4") (pinfunction "PX16_/_PX53_D4") (pintype "bidirectional+no_connect"))
    )
    (net (code "111") (name "unconnected-(U900-PX23-PadK1)") (class "Default")
      (node (ref "U900") (pin "K1") (pinfunction "PX23_K1") (pintype "bidirectional+no_connect"))
    )
    (net (code "112") (name "unconnected-(U900-PX24-PadJ2)") (class "Default")
      (node (ref "U900") (pin "J2") (pinfunction "PX24_J2") (pintype "bidirectional+no_connect"))
    )
    (net (code "113") (name "unconnected-(U900-PX25-PadH4)") (class "Default")
      (node (ref "U900") (pin "H4") (pinfunction "PX25_H4") (pintype "bidirectional+no_connect"))
    )
    (net (code "114") (name "unconnected-(U900-PX26-PadJ3)") (class "Default")
      (node (ref "U900") (pin "J3") (pinfunction "PX26_J3") (pintype "bidirectional+no_connect"))
    )
    (net (code "115") (name "unconnected-(U900-PX31-PadH5)") (class "Default")
      (node (ref "U900") (pin "H5") (pinfunction "PX31_H5") (pintype "bidirectional+no_connect"))
    )
  )
)
